# denmark.net
KiCad netlist of a schematic drawn in EAGLE
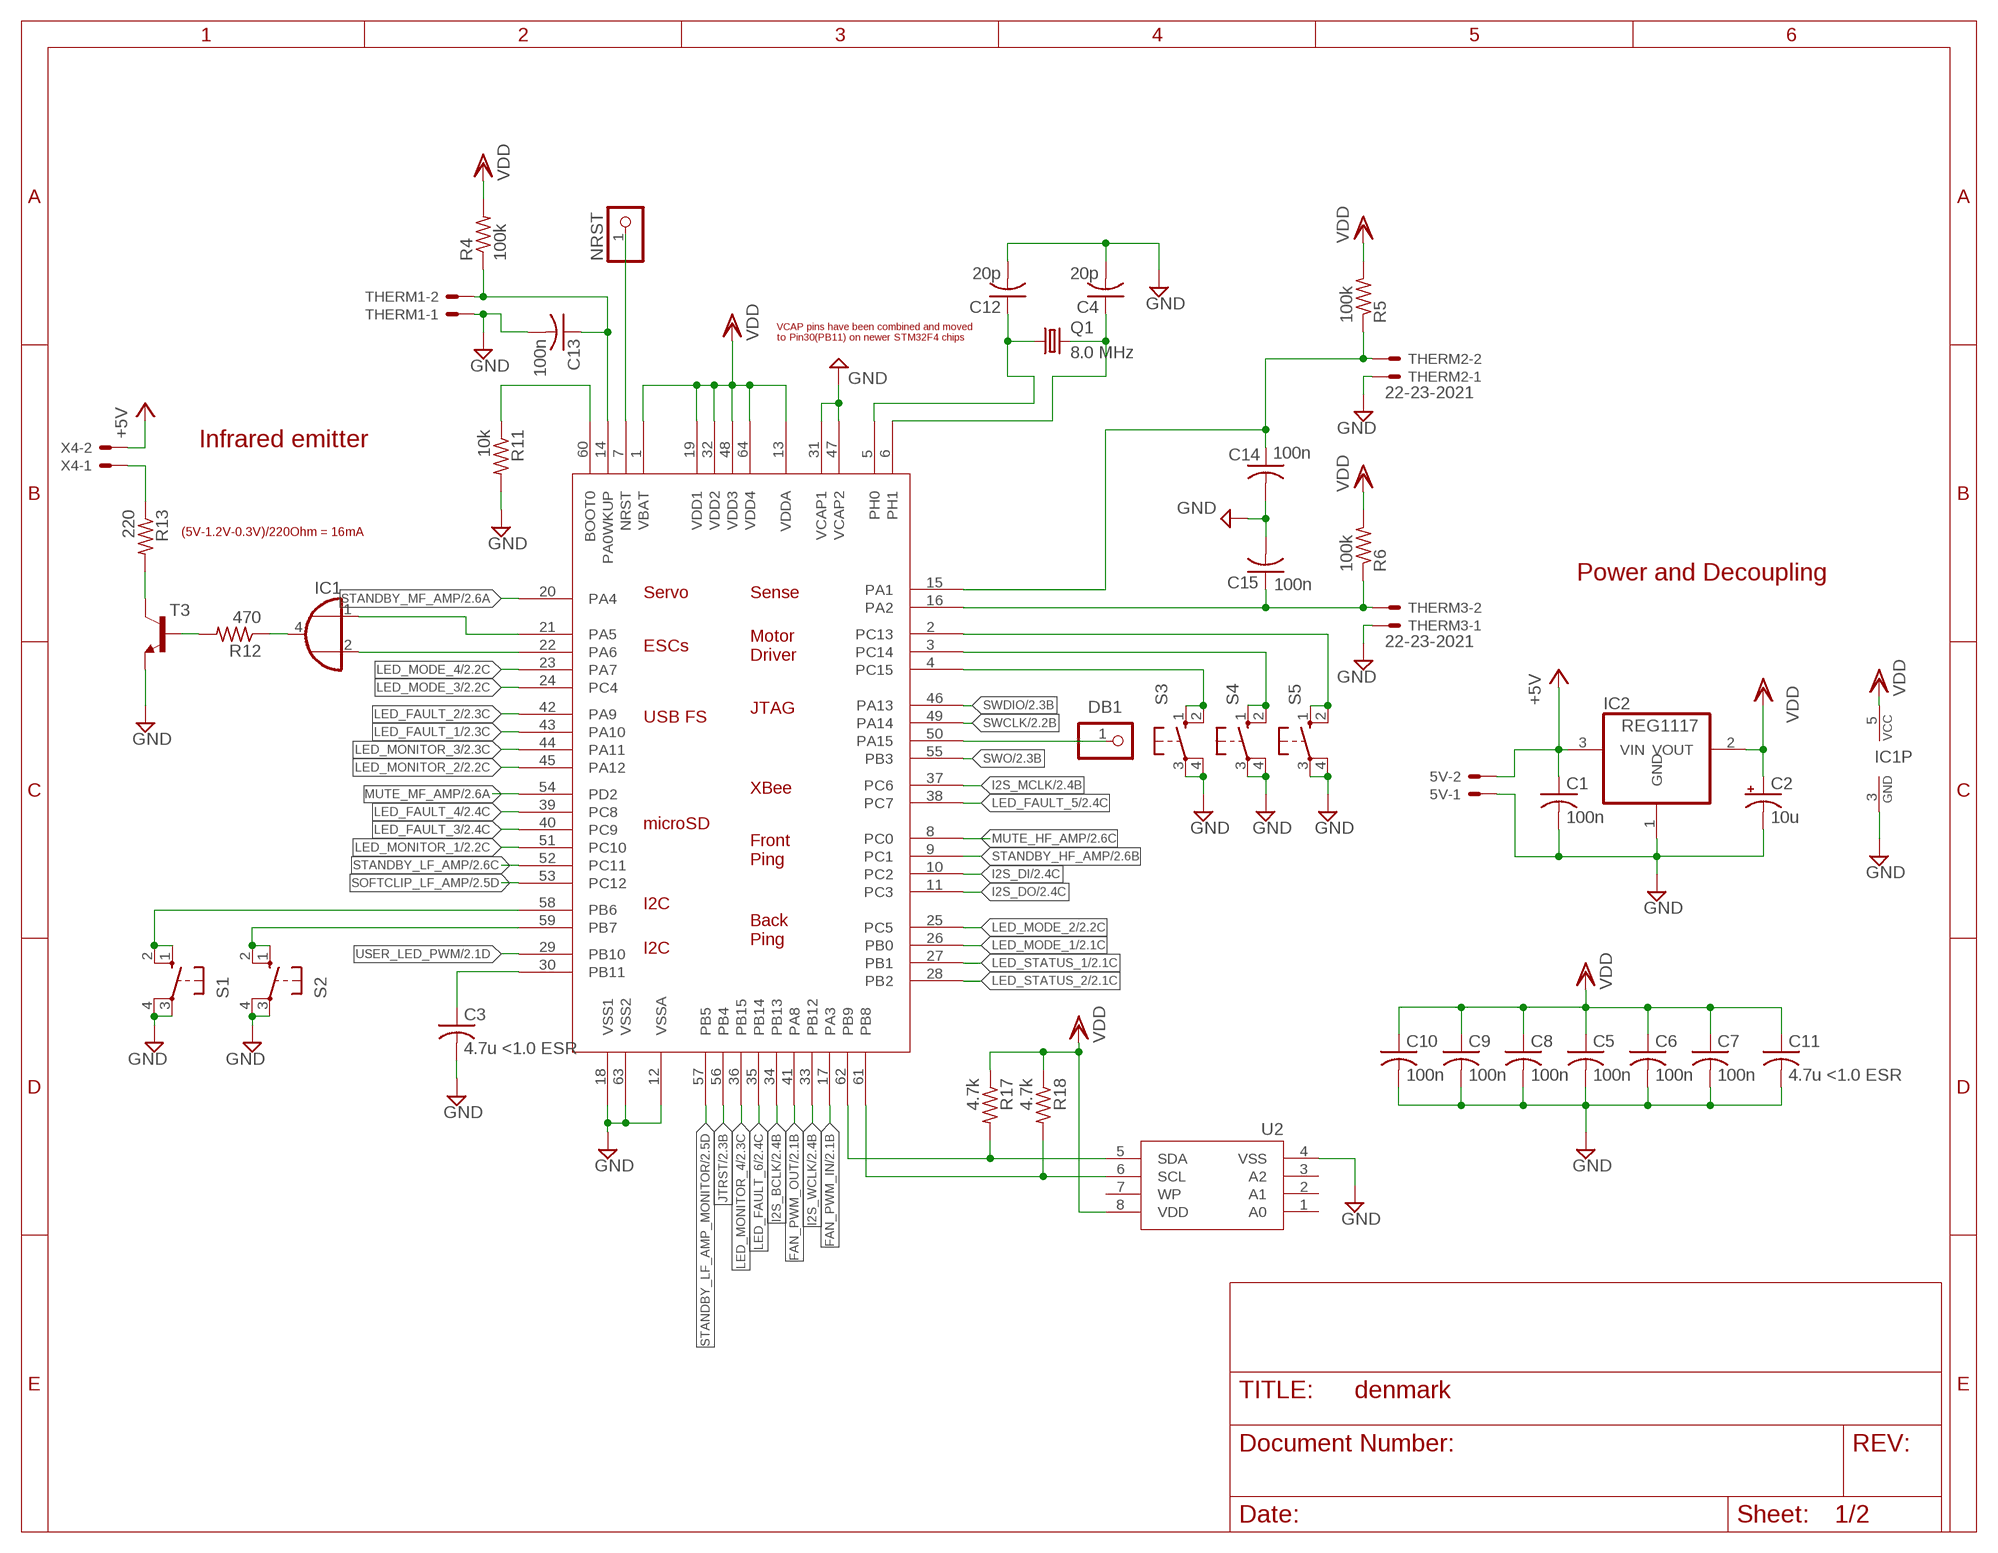
[diagram p0: schematic, sheet 1]
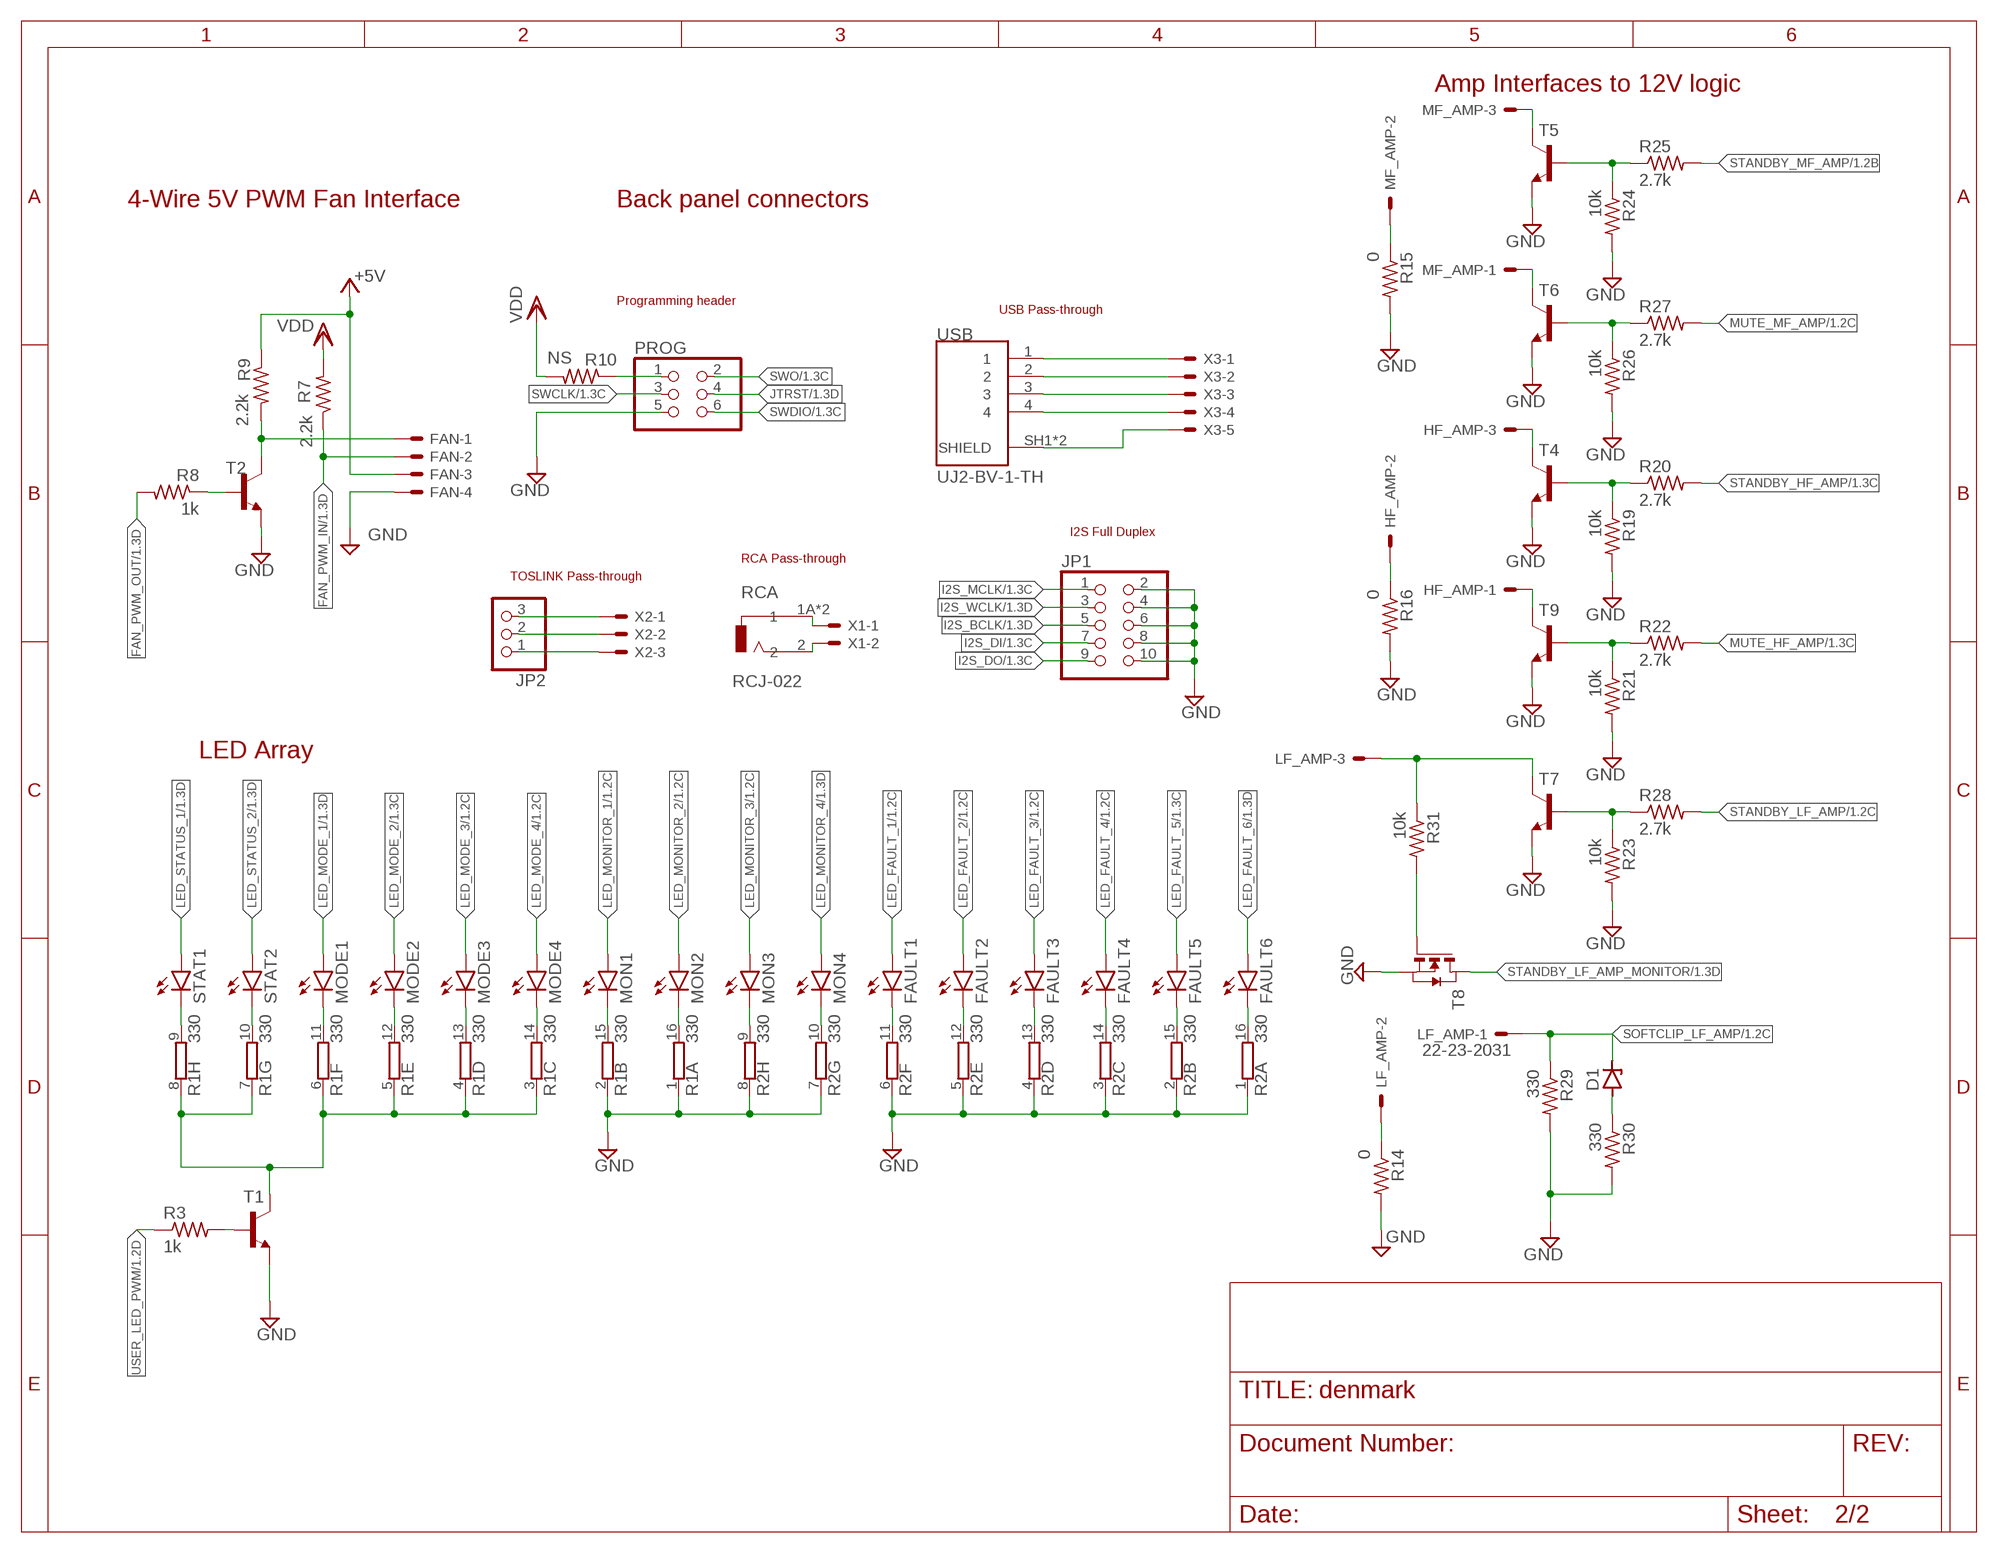
[diagram p1: schematic, sheet 2]

(export (version "E")
  (design (tool "Eeschema 10.0.6"))
  (components
    (comp (ref "D1")
      (value "ZENER-DIODESOD80C")
      (footprint "eagle-import:SOD80C")
      (libsource (lib "eagle-import") (part "ZENER-DIODESOD80C"))
    )
    (comp (ref "FAN")
      (value "22-23-2041")
      (footprint "eagle-import:22-23-2041")
      (fields (field (name "MF") "MOLEX"))
      (libsource (lib "eagle-import") (part "22-23-2041"))
    )
    (comp (ref "FAULT1")
      (value "LEDCHIPLED_0805")
      (footprint "eagle-import:CHIPLED_0805")
      (libsource (lib "eagle-import") (part "LEDCHIPLED_0805"))
    )
    (comp (ref "FAULT2")
      (value "LEDCHIPLED_0805")
      (footprint "eagle-import:CHIPLED_0805")
      (libsource (lib "eagle-import") (part "LEDCHIPLED_0805"))
    )
    (comp (ref "FAULT3")
      (value "LEDCHIPLED_0805")
      (footprint "eagle-import:CHIPLED_0805")
      (libsource (lib "eagle-import") (part "LEDCHIPLED_0805"))
    )
    (comp (ref "FAULT4")
      (value "LEDCHIPLED_0805")
      (footprint "eagle-import:CHIPLED_0805")
      (libsource (lib "eagle-import") (part "LEDCHIPLED_0805"))
    )
    (comp (ref "FAULT5")
      (value "LEDCHIPLED_0805")
      (footprint "eagle-import:CHIPLED_0805")
      (libsource (lib "eagle-import") (part "LEDCHIPLED_0805"))
    )
    (comp (ref "FAULT6")
      (value "LEDCHIPLED_0805")
      (footprint "eagle-import:CHIPLED_0805")
      (libsource (lib "eagle-import") (part "LEDCHIPLED_0805"))
    )
    (comp (ref "HF_AMP")
      (value "22-23-2031")
      (footprint "eagle-import:22-23-2031")
      (fields (field (name "MF") "MOLEX"))
      (libsource (lib "eagle-import") (part "22-23-2031"))
    )
    (comp (ref "JP1")
      (value "PINHD-2X5")
      (footprint "eagle-import:2X05")
      (libsource (lib "eagle-import") (part "PINHD-2X5"))
    )
    (comp (ref "JP2")
      (value "PINHD-1X3")
      (footprint "eagle-import:1X03")
      (libsource (lib "eagle-import") (part "PINHD-1X3"))
    )
    (comp (ref "LF_AMP")
      (value "22-23-2031")
      (footprint "eagle-import:22-23-2031")
      (fields (field (name "MF") "MOLEX"))
      (libsource (lib "eagle-import") (part "22-23-2031"))
    )
    (comp (ref "MF_AMP")
      (value "22-23-2031")
      (footprint "eagle-import:22-23-2031")
      (fields (field (name "MF") "MOLEX"))
      (libsource (lib "eagle-import") (part "22-23-2031"))
    )
    (comp (ref "MODE1")
      (value "LEDCHIPLED_0805")
      (footprint "eagle-import:CHIPLED_0805")
      (libsource (lib "eagle-import") (part "LEDCHIPLED_0805"))
    )
    (comp (ref "MODE2")
      (value "LEDCHIPLED_0805")
      (footprint "eagle-import:CHIPLED_0805")
      (libsource (lib "eagle-import") (part "LEDCHIPLED_0805"))
    )
    (comp (ref "MODE3")
      (value "LEDCHIPLED_0805")
      (footprint "eagle-import:CHIPLED_0805")
      (libsource (lib "eagle-import") (part "LEDCHIPLED_0805"))
    )
    (comp (ref "MODE4")
      (value "LEDCHIPLED_0805")
      (footprint "eagle-import:CHIPLED_0805")
      (libsource (lib "eagle-import") (part "LEDCHIPLED_0805"))
    )
    (comp (ref "MON1")
      (value "LEDCHIPLED_0805")
      (footprint "eagle-import:CHIPLED_0805")
      (libsource (lib "eagle-import") (part "LEDCHIPLED_0805"))
    )
    (comp (ref "MON2")
      (value "LEDCHIPLED_0805")
      (footprint "eagle-import:CHIPLED_0805")
      (libsource (lib "eagle-import") (part "LEDCHIPLED_0805"))
    )
    (comp (ref "MON3")
      (value "LEDCHIPLED_0805")
      (footprint "eagle-import:CHIPLED_0805")
      (libsource (lib "eagle-import") (part "LEDCHIPLED_0805"))
    )
    (comp (ref "MON4")
      (value "LEDCHIPLED_0805")
      (footprint "eagle-import:CHIPLED_0805")
      (libsource (lib "eagle-import") (part "LEDCHIPLED_0805"))
    )
    (comp (ref "PROG")
      (value "PINHD-2X3")
      (footprint "eagle-import:2X03")
      (libsource (lib "eagle-import") (part "PINHD-2X3"))
    )
    (comp (ref "R1")
      (value "330")
      (footprint "eagle-import:SO16")
      (libsource (lib "eagle-import") (part "2NBS16-8E"))
    )
    (comp (ref "R2")
      (value "330")
      (footprint "eagle-import:SO16")
      (libsource (lib "eagle-import") (part "2NBS16-8E"))
    )
    (comp (ref "R3")
      (value "1k")
      (footprint "eagle-import:R0603")
      (libsource (lib "eagle-import") (part "R-US_R0603"))
    )
    (comp (ref "R7")
      (value "2.2k")
      (footprint "eagle-import:R0603")
      (libsource (lib "eagle-import") (part "R-US_R0603"))
    )
    (comp (ref "R8")
      (value "1k")
      (footprint "eagle-import:R0603")
      (libsource (lib "eagle-import") (part "R-US_R0603"))
    )
    (comp (ref "R9")
      (value "2.2k")
      (footprint "eagle-import:R0603")
      (libsource (lib "eagle-import") (part "R-US_R0603"))
    )
    (comp (ref "R10")
      (value "NS")
      (footprint "eagle-import:R0603")
      (libsource (lib "eagle-import") (part "R-US_R0603"))
    )
    (comp (ref "R14")
      (value "0")
      (footprint "eagle-import:R0603")
      (libsource (lib "eagle-import") (part "R-US_R0603"))
    )
    (comp (ref "R15")
      (value "0")
      (footprint "eagle-import:R0603")
      (libsource (lib "eagle-import") (part "R-US_R0603"))
    )
    (comp (ref "R16")
      (value "0")
      (footprint "eagle-import:R0603")
      (libsource (lib "eagle-import") (part "R-US_R0603"))
    )
    (comp (ref "R19")
      (value "10k")
      (footprint "eagle-import:R0603")
      (libsource (lib "eagle-import") (part "R-US_R0603"))
    )
    (comp (ref "R20")
      (value "2.7k")
      (footprint "eagle-import:R0603")
      (libsource (lib "eagle-import") (part "R-US_R0603"))
    )
    (comp (ref "R21")
      (value "10k")
      (footprint "eagle-import:R0603")
      (libsource (lib "eagle-import") (part "R-US_R0603"))
    )
    (comp (ref "R22")
      (value "2.7k")
      (footprint "eagle-import:R0603")
      (libsource (lib "eagle-import") (part "R-US_R0603"))
    )
    (comp (ref "R23")
      (value "10k")
      (footprint "eagle-import:R0603")
      (libsource (lib "eagle-import") (part "R-US_R0603"))
    )
    (comp (ref "R24")
      (value "10k")
      (footprint "eagle-import:R0603")
      (libsource (lib "eagle-import") (part "R-US_R0603"))
    )
    (comp (ref "R25")
      (value "2.7k")
      (footprint "eagle-import:R0603")
      (libsource (lib "eagle-import") (part "R-US_R0603"))
    )
    (comp (ref "R26")
      (value "10k")
      (footprint "eagle-import:R0603")
      (libsource (lib "eagle-import") (part "R-US_R0603"))
    )
    (comp (ref "R27")
      (value "2.7k")
      (footprint "eagle-import:R0603")
      (libsource (lib "eagle-import") (part "R-US_R0603"))
    )
    (comp (ref "R28")
      (value "2.7k")
      (footprint "eagle-import:R0603")
      (libsource (lib "eagle-import") (part "R-US_R0603"))
    )
    (comp (ref "R29")
      (value "330")
      (footprint "eagle-import:R0603")
      (libsource (lib "eagle-import") (part "R-US_R0603"))
    )
    (comp (ref "R30")
      (value "330")
      (footprint "eagle-import:R0603")
      (libsource (lib "eagle-import") (part "R-US_R0603"))
    )
    (comp (ref "R31")
      (value "10k")
      (footprint "eagle-import:R0603")
      (libsource (lib "eagle-import") (part "R-US_R0603"))
    )
    (comp (ref "RCA")
      (value "RCJ-022")
      (footprint "eagle-import:CUI_RCJ-022")
      (fields (field (name "MANUFACTURER") "CUI Inc"))
      (libsource (lib "eagle-import") (part "RCJ-022"))
    )
    (comp (ref "STAT1")
      (value "LEDCHIPLED_0805")
      (footprint "eagle-import:CHIPLED_0805")
      (libsource (lib "eagle-import") (part "LEDCHIPLED_0805"))
    )
    (comp (ref "STAT2")
      (value "LEDCHIPLED_0805")
      (footprint "eagle-import:CHIPLED_0805")
      (libsource (lib "eagle-import") (part "LEDCHIPLED_0805"))
    )
    (comp (ref "T1")
      (value "MMBT3904LT1-NPN-SOT23-BEC")
      (footprint "eagle-import:SOT23-BEC")
      (libsource (lib "eagle-import") (part "-NPN-SOT23-BECMMBT3904LT1"))
    )
    (comp (ref "T2")
      (value "MMBT3904LT1-NPN-SOT23-BEC")
      (footprint "eagle-import:SOT23-BEC")
      (libsource (lib "eagle-import") (part "-NPN-SOT23-BECMMBT3904LT1"))
    )
    (comp (ref "T4")
      (value "MMBT3904LT1-NPN-SOT23-BEC")
      (footprint "eagle-import:SOT23-BEC")
      (libsource (lib "eagle-import") (part "-NPN-SOT23-BECMMBT3904LT1"))
    )
    (comp (ref "T5")
      (value "MMBT3904LT1-NPN-SOT23-BEC")
      (footprint "eagle-import:SOT23-BEC")
      (libsource (lib "eagle-import") (part "-NPN-SOT23-BECMMBT3904LT1"))
    )
    (comp (ref "T6")
      (value "MMBT3904LT1-NPN-SOT23-BEC")
      (footprint "eagle-import:SOT23-BEC")
      (libsource (lib "eagle-import") (part "-NPN-SOT23-BECMMBT3904LT1"))
    )
    (comp (ref "T7")
      (value "MMBT3904LT1-NPN-SOT23-BEC")
      (footprint "eagle-import:SOT23-BEC")
      (libsource (lib "eagle-import") (part "-NPN-SOT23-BECMMBT3904LT1"))
    )
    (comp (ref "T8")
      (value "NMOSSOT23")
      (footprint "eagle-import:SOT-23")
      (libsource (lib "eagle-import") (part "NMOSSOT23"))
    )
    (comp (ref "T9")
      (value "MMBT3904LT1-NPN-SOT23-BEC")
      (footprint "eagle-import:SOT23-BEC")
      (libsource (lib "eagle-import") (part "-NPN-SOT23-BECMMBT3904LT1"))
    )
    (comp (ref "USB")
      (value "UJ2-BV-1-TH")
      (footprint "eagle-import:CUI_UJ2-BV-1-TH")
      (fields (field (name "MANUFACTURER") "CUI INC"))
      (libsource (lib "eagle-import") (part "UJ2-BV-1-TH"))
    )
    (comp (ref "X1")
      (value "22-23-2021")
      (footprint "eagle-import:22-23-2021")
      (fields (field (name "MF") "MOLEX"))
      (libsource (lib "eagle-import") (part "22-23-2021"))
    )
    (comp (ref "X2")
      (value "22-23-2031")
      (footprint "eagle-import:22-23-2031")
      (fields (field (name "MF") "MOLEX"))
      (libsource (lib "eagle-import") (part "22-23-2031"))
    )
    (comp (ref "X3")
      (value "22-23-2051")
      (footprint "eagle-import:22-23-2051")
      (fields (field (name "MF") "MOLEX"))
      (libsource (lib "eagle-import") (part "22-23-2051"))
    )
    (comp (ref "5V")
      (value "22-23-2021")
      (footprint "eagle-import:22-23-2021")
      (fields (field (name "MF") "MOLEX"))
      (libsource (lib "eagle-import") (part "22-23-2021"))
    )
    (comp (ref "C1")
      (value "100n")
      (footprint "eagle-import:C0805")
      (libsource (lib "eagle-import") (part "C-USC0805"))
    )
    (comp (ref "C2")
      (value "10u")
      (footprint "eagle-import:E3,5-8")
      (libsource (lib "eagle-import") (part "CPOL-USE3.5-8"))
    )
    (comp (ref "C3")
      (value "4.7u <1.0 ESR")
      (footprint "eagle-import:C1206")
      (libsource (lib "eagle-import") (part "C-USC1206"))
    )
    (comp (ref "C4")
      (value "20p")
      (footprint "eagle-import:C0603K")
      (libsource (lib "eagle-import") (part "C-USC0603K"))
    )
    (comp (ref "C5")
      (value "100n")
      (footprint "eagle-import:C0603K")
      (libsource (lib "eagle-import") (part "C-USC0603K"))
    )
    (comp (ref "C6")
      (value "100n")
      (footprint "eagle-import:C0603K")
      (libsource (lib "eagle-import") (part "C-USC0603K"))
    )
    (comp (ref "C7")
      (value "100n")
      (footprint "eagle-import:C0603K")
      (libsource (lib "eagle-import") (part "C-USC0603K"))
    )
    (comp (ref "C8")
      (value "100n")
      (footprint "eagle-import:C0603K")
      (libsource (lib "eagle-import") (part "C-USC0603K"))
    )
    (comp (ref "C9")
      (value "100n")
      (footprint "eagle-import:C0603K")
      (libsource (lib "eagle-import") (part "C-USC0603K"))
    )
    (comp (ref "C10")
      (value "100n")
      (footprint "eagle-import:C0603K")
      (libsource (lib "eagle-import") (part "C-USC0603K"))
    )
    (comp (ref "C11")
      (value "4.7u <1.0 ESR")
      (footprint "eagle-import:C1206")
      (libsource (lib "eagle-import") (part "C-USC1206"))
    )
    (comp (ref "C12")
      (value "20p")
      (footprint "eagle-import:C0603K")
      (libsource (lib "eagle-import") (part "C-USC0603K"))
    )
    (comp (ref "C13")
      (value "100n")
      (footprint "eagle-import:C0603K")
      (libsource (lib "eagle-import") (part "C-USC0603K"))
    )
    (comp (ref "C14")
      (value "100n")
      (footprint "eagle-import:C0603K")
      (libsource (lib "eagle-import") (part "C-USC0603K"))
    )
    (comp (ref "C15")
      (value "100n")
      (footprint "eagle-import:C0603K")
      (libsource (lib "eagle-import") (part "C-USC0603K"))
    )
    (comp (ref "DB1")
      (value "PINHD-1X1")
      (footprint "eagle-import:1X01")
      (libsource (lib "eagle-import") (part "PINHD-1X1"))
    )
    (comp (ref "IC1")
      (value "74AHC1G32DBV")
      (footprint "eagle-import:SOT23-5")
      (libsource (lib "eagle-import") (part "741G32DBVAHC"))
    )
    (comp (ref "IC2")
      (value "REG1117")
      (footprint "eagle-import:SOT223")
      (libsource (lib "eagle-import") (part "REG1117"))
    )
    (comp (ref "NRST")
      (value "PINHD-1X1")
      (footprint "eagle-import:1X01")
      (libsource (lib "eagle-import") (part "PINHD-1X1"))
    )
    (comp (ref "Q1")
      (value "8.0 MHz")
      (footprint "eagle-import:HC49U-V")
      (libsource (lib "eagle-import") (part "CRYSTALHC49U-V"))
    )
    (comp (ref "R4")
      (value "100k")
      (footprint "eagle-import:R0603")
      (libsource (lib "eagle-import") (part "R-US_R0603"))
    )
    (comp (ref "R5")
      (value "100k")
      (footprint "eagle-import:R0603")
      (libsource (lib "eagle-import") (part "R-US_R0603"))
    )
    (comp (ref "R6")
      (value "100k")
      (footprint "eagle-import:R0603")
      (libsource (lib "eagle-import") (part "R-US_R0603"))
    )
    (comp (ref "R11")
      (value "10k")
      (footprint "eagle-import:R0603")
      (libsource (lib "eagle-import") (part "R-US_R0603"))
    )
    (comp (ref "R12")
      (value "470")
      (footprint "eagle-import:R0603")
      (libsource (lib "eagle-import") (part "R-US_R0603"))
    )
    (comp (ref "R13")
      (value "220")
      (footprint "eagle-import:R0603")
      (libsource (lib "eagle-import") (part "R-US_R0603"))
    )
    (comp (ref "R17")
      (value "4.7k")
      (footprint "eagle-import:R0603")
      (libsource (lib "eagle-import") (part "R-US_R0603"))
    )
    (comp (ref "R18")
      (value "4.7k")
      (footprint "eagle-import:R0603")
      (libsource (lib "eagle-import") (part "R-US_R0603"))
    )
    (comp (ref "S1")
      (value "10-XX")
      (footprint "eagle-import:B3F-10XX")
      (fields (field (name "MPN") "B3F-1000"))
      (libsource (lib "eagle-import") (part "10-XX"))
    )
    (comp (ref "S2")
      (value "10-XX")
      (footprint "eagle-import:B3F-10XX")
      (fields (field (name "MPN") "B3F-1000"))
      (libsource (lib "eagle-import") (part "10-XX"))
    )
    (comp (ref "S3")
      (value "10-XX")
      (footprint "eagle-import:B3F-10XX")
      (fields (field (name "MPN") "B3F-1000"))
      (libsource (lib "eagle-import") (part "10-XX"))
    )
    (comp (ref "S4")
      (value "10-XX")
      (footprint "eagle-import:B3F-10XX")
      (fields (field (name "MPN") "B3F-1000"))
      (libsource (lib "eagle-import") (part "10-XX"))
    )
    (comp (ref "S5")
      (value "10-XX")
      (footprint "eagle-import:B3F-10XX")
      (fields (field (name "MPN") "B3F-1000"))
      (libsource (lib "eagle-import") (part "10-XX"))
    )
    (comp (ref "T3")
      (value "MMBT3904LT1-NPN-SOT23-BEC")
      (footprint "eagle-import:SOT23-BEC")
      (libsource (lib "eagle-import") (part "-NPN-SOT23-BECMMBT3904LT1"))
    )
    (comp (ref "THERM1")
      (value "22-23-2021")
      (footprint "eagle-import:22-23-2021")
      (fields (field (name "MF") "MOLEX"))
      (libsource (lib "eagle-import") (part "22-23-2021"))
    )
    (comp (ref "THERM2")
      (value "22-23-2021")
      (footprint "eagle-import:22-23-2021")
      (fields (field (name "MF") "MOLEX"))
      (libsource (lib "eagle-import") (part "22-23-2021"))
    )
    (comp (ref "THERM3")
      (value "22-23-2021")
      (footprint "eagle-import:22-23-2021")
      (fields (field (name "MF") "MOLEX"))
      (libsource (lib "eagle-import") (part "22-23-2021"))
    )
    (comp (ref "U1")
      (value "STM32F4_10X10_LQFP64")
      (footprint "eagle-import:LQFP-ST-64-2")
      (libsource (lib "eagle-import") (part "STM32F4_10X10_LQFP64"))
    )
    (comp (ref "U2")
      (value "MB85RCSOIC8")
      (footprint "eagle-import:SOIC8")
      (libsource (lib "eagle-import") (part "MB85RCSOIC8"))
    )
    (comp (ref "X4")
      (value "22-23-2021")
      (footprint "eagle-import:22-23-2021")
      (fields (field (name "MF") "MOLEX"))
      (libsource (lib "eagle-import") (part "22-23-2021"))
    )
  )
  (nets
    (net (code "1") (name "+5V") (class "Default")
      (node (ref "5V") (pin "2") (pinfunction "S_2") (pintype "passive"))
      (node (ref "C1") (pin "1") (pinfunction "1_1") (pintype "passive"))
      (node (ref "FAN") (pin "3") (pinfunction "S_3") (pintype "passive"))
      (node (ref "IC2") (pin "3") (pinfunction "VIN_3") (pintype "input"))
      (node (ref "R9") (pin "1") (pinfunction "1_1") (pintype "passive"))
      (node (ref "X4") (pin "2") (pinfunction "S_2") (pintype "passive"))
    )
    (net (code "2") (name "FAN_PWM_IN") (class "Default")
      (node (ref "FAN") (pin "2") (pinfunction "S_2") (pintype "passive"))
      (node (ref "R7") (pin "1") (pinfunction "1_1") (pintype "passive"))
      (node (ref "U1") (pin "17") (pinfunction "PA3_17") (pintype "bidirectional"))
    )
    (net (code "3") (name "FAN_PWM_OUT") (class "Default")
      (node (ref "R8") (pin "2") (pinfunction "2_2") (pintype "passive"))
      (node (ref "U1") (pin "41") (pinfunction "PA8_41") (pintype "bidirectional"))
    )
    (net (code "4") (name "GND") (class "Default")
      (node (ref "5V") (pin "1") (pinfunction "S_1") (pintype "passive"))
      (node (ref "C1") (pin "2") (pinfunction "2_2") (pintype "passive"))
      (node (ref "C10") (pin "2") (pinfunction "2_2") (pintype "passive"))
      (node (ref "C11") (pin "2") (pinfunction "2_2") (pintype "passive"))
      (node (ref "C12") (pin "2") (pinfunction "2_2") (pintype "passive"))
      (node (ref "C13") (pin "2") (pinfunction "2_2") (pintype "passive"))
      (node (ref "C14") (pin "2") (pinfunction "2_2") (pintype "passive"))
      (node (ref "C15") (pin "2") (pinfunction "2_2") (pintype "passive"))
      (node (ref "C2") (pin "-") (pinfunction "-_-") (pintype "passive"))
      (node (ref "C3") (pin "2") (pinfunction "2_2") (pintype "passive"))
      (node (ref "C4") (pin "2") (pinfunction "2_2") (pintype "passive"))
      (node (ref "C5") (pin "2") (pinfunction "2_2") (pintype "passive"))
      (node (ref "C6") (pin "2") (pinfunction "2_2") (pintype "passive"))
      (node (ref "C7") (pin "2") (pinfunction "2_2") (pintype "passive"))
      (node (ref "C8") (pin "2") (pinfunction "2_2") (pintype "passive"))
      (node (ref "C9") (pin "2") (pinfunction "2_2") (pintype "passive"))
      (node (ref "FAN") (pin "4") (pinfunction "S_4") (pintype "passive"))
      (node (ref "IC1") (pin "3") (pinfunction "GND_3") (pintype "power_in"))
      (node (ref "IC2") (pin "1") (pinfunction "GND_1") (pintype "power_in"))
      (node (ref "JP1") (pin "10") (pinfunction "10_10") (pintype "passive"))
      (node (ref "JP1") (pin "2") (pinfunction "2_2") (pintype "passive"))
      (node (ref "JP1") (pin "4") (pinfunction "4_4") (pintype "passive"))
      (node (ref "JP1") (pin "6") (pinfunction "6_6") (pintype "passive"))
      (node (ref "JP1") (pin "8") (pinfunction "8_8") (pintype "passive"))
      (node (ref "PROG") (pin "5") (pinfunction "5_5") (pintype "passive"))
      (node (ref "R1") (pin "1") (pinfunction "1_1") (pintype "passive"))
      (node (ref "R1") (pin "2") (pinfunction "1_2") (pintype "passive"))
      (node (ref "R11") (pin "2") (pinfunction "2_2") (pintype "passive"))
      (node (ref "R14") (pin "2") (pinfunction "2_2") (pintype "passive"))
      (node (ref "R15") (pin "2") (pinfunction "2_2") (pintype "passive"))
      (node (ref "R16") (pin "2") (pinfunction "2_2") (pintype "passive"))
      (node (ref "R19") (pin "2") (pinfunction "2_2") (pintype "passive"))
      (node (ref "R2") (pin "1") (pinfunction "1_1") (pintype "passive"))
      (node (ref "R2") (pin "2") (pinfunction "1_2") (pintype "passive"))
      (node (ref "R2") (pin "3") (pinfunction "1_3") (pintype "passive"))
      (node (ref "R2") (pin "4") (pinfunction "1_4") (pintype "passive"))
      (node (ref "R2") (pin "5") (pinfunction "1_5") (pintype "passive"))
      (node (ref "R2") (pin "6") (pinfunction "1_6") (pintype "passive"))
      (node (ref "R2") (pin "7") (pinfunction "1_7") (pintype "passive"))
      (node (ref "R2") (pin "8") (pinfunction "1_8") (pintype "passive"))
      (node (ref "R21") (pin "2") (pinfunction "2_2") (pintype "passive"))
      (node (ref "R23") (pin "2") (pinfunction "2_2") (pintype "passive"))
      (node (ref "R24") (pin "2") (pinfunction "2_2") (pintype "passive"))
      (node (ref "R26") (pin "2") (pinfunction "2_2") (pintype "passive"))
      (node (ref "R29") (pin "2") (pinfunction "2_2") (pintype "passive"))
      (node (ref "R30") (pin "2") (pinfunction "2_2") (pintype "passive"))
      (node (ref "S1") (pin "3") (pinfunction "P_3") (pintype "passive"))
      (node (ref "S1") (pin "4") (pinfunction "P1_4") (pintype "passive"))
      (node (ref "S2") (pin "3") (pinfunction "P_3") (pintype "passive"))
      (node (ref "S2") (pin "4") (pinfunction "P1_4") (pintype "passive"))
      (node (ref "S3") (pin "3") (pinfunction "P_3") (pintype "passive"))
      (node (ref "S3") (pin "4") (pinfunction "P1_4") (pintype "passive"))
      (node (ref "S4") (pin "3") (pinfunction "P_3") (pintype "passive"))
      (node (ref "S4") (pin "4") (pinfunction "P1_4") (pintype "passive"))
      (node (ref "S5") (pin "3") (pinfunction "P_3") (pintype "passive"))
      (node (ref "S5") (pin "4") (pinfunction "P1_4") (pintype "passive"))
      (node (ref "T1") (pin "E") (pinfunction "E_E") (pintype "passive"))
      (node (ref "T2") (pin "E") (pinfunction "E_E") (pintype "passive"))
      (node (ref "T3") (pin "E") (pinfunction "E_E") (pintype "passive"))
      (node (ref "T4") (pin "E") (pinfunction "E_E") (pintype "passive"))
      (node (ref "T5") (pin "E") (pinfunction "E_E") (pintype "passive"))
      (node (ref "T6") (pin "E") (pinfunction "E_E") (pintype "passive"))
      (node (ref "T7") (pin "E") (pinfunction "E_E") (pintype "passive"))
      (node (ref "T8") (pin "2") (pinfunction "S_2") (pintype "passive"))
      (node (ref "T9") (pin "E") (pinfunction "E_E") (pintype "passive"))
      (node (ref "THERM1") (pin "1") (pinfunction "S_1") (pintype "passive"))
      (node (ref "THERM2") (pin "1") (pinfunction "S_1") (pintype "passive"))
      (node (ref "THERM3") (pin "1") (pinfunction "S_1") (pintype "passive"))
      (node (ref "U1") (pin "12") (pinfunction "VSSA_12") (pintype "power_in"))
      (node (ref "U1") (pin "18") (pinfunction "VSS1_18") (pintype "power_in"))
      (node (ref "U1") (pin "31") (pinfunction "VCAP1_31") (pintype "bidirectional"))
      (node (ref "U1") (pin "47") (pinfunction "VCAP2_47") (pintype "bidirectional"))
      (node (ref "U1") (pin "63") (pinfunction "VSS2_63") (pintype "power_in"))
      (node (ref "U2") (pin "4") (pinfunction "VSS_4") (pintype "bidirectional"))
    )
    (net (code "5") (name "I2S_BCLK") (class "Default")
      (node (ref "JP1") (pin "5") (pinfunction "5_5") (pintype "passive"))
      (node (ref "U1") (pin "34") (pinfunction "PB13_34") (pintype "bidirectional"))
    )
    (net (code "6") (name "I2S_DI") (class "Default")
      (node (ref "JP1") (pin "7") (pinfunction "7_7") (pintype "passive"))
      (node (ref "U1") (pin "10") (pinfunction "PC2_10") (pintype "bidirectional"))
    )
    (net (code "7") (name "I2S_DO") (class "Default")
      (node (ref "JP1") (pin "9") (pinfunction "9_9") (pintype "passive"))
      (node (ref "U1") (pin "11") (pinfunction "PC3_11") (pintype "bidirectional"))
    )
    (net (code "8") (name "I2S_MCLK") (class "Default")
      (node (ref "JP1") (pin "1") (pinfunction "1_1") (pintype "passive"))
      (node (ref "U1") (pin "37") (pinfunction "PC6_37") (pintype "bidirectional"))
    )
    (net (code "9") (name "I2S_WCLK") (class "Default")
      (node (ref "JP1") (pin "3") (pinfunction "3_3") (pintype "passive"))
      (node (ref "U1") (pin "33") (pinfunction "PB12_33") (pintype "bidirectional"))
    )
    (net (code "10") (name "JTRST") (class "Default")
      (node (ref "PROG") (pin "4") (pinfunction "4_4") (pintype "passive"))
      (node (ref "U1") (pin "56") (pinfunction "PB4_56") (pintype "bidirectional"))
    )
    (net (code "11") (name "LED_FAULT_1") (class "Default")
      (node (ref "FAULT1") (pin "A") (pinfunction "A_A") (pintype "passive"))
      (node (ref "U1") (pin "43") (pinfunction "PA10_43") (pintype "bidirectional"))
    )
    (net (code "12") (name "LED_FAULT_2") (class "Default")
      (node (ref "FAULT2") (pin "A") (pinfunction "A_A") (pintype "passive"))
      (node (ref "U1") (pin "42") (pinfunction "PA9_42") (pintype "bidirectional"))
    )
    (net (code "13") (name "LED_FAULT_3") (class "Default")
      (node (ref "FAULT3") (pin "A") (pinfunction "A_A") (pintype "passive"))
      (node (ref "U1") (pin "40") (pinfunction "PC9_40") (pintype "bidirectional"))
    )
    (net (code "14") (name "LED_FAULT_4") (class "Default")
      (node (ref "FAULT4") (pin "A") (pinfunction "A_A") (pintype "passive"))
      (node (ref "U1") (pin "39") (pinfunction "PC8_39") (pintype "bidirectional"))
    )
    (net (code "15") (name "LED_FAULT_5") (class "Default")
      (node (ref "FAULT5") (pin "A") (pinfunction "A_A") (pintype "passive"))
      (node (ref "U1") (pin "38") (pinfunction "PC7_38") (pintype "bidirectional"))
    )
    (net (code "16") (name "LED_FAULT_6") (class "Default")
      (node (ref "FAULT6") (pin "A") (pinfunction "A_A") (pintype "passive"))
      (node (ref "U1") (pin "35") (pinfunction "PB14_35") (pintype "bidirectional"))
    )
    (net (code "17") (name "LED_MODE_1") (class "Default")
      (node (ref "MODE1") (pin "A") (pinfunction "A_A") (pintype "passive"))
      (node (ref "U1") (pin "26") (pinfunction "PB0_26") (pintype "bidirectional"))
    )
    (net (code "18") (name "LED_MODE_2") (class "Default")
      (node (ref "MODE2") (pin "A") (pinfunction "A_A") (pintype "passive"))
      (node (ref "U1") (pin "25") (pinfunction "PC5_25") (pintype "bidirectional"))
    )
    (net (code "19") (name "LED_MODE_3") (class "Default")
      (node (ref "MODE3") (pin "A") (pinfunction "A_A") (pintype "passive"))
      (node (ref "U1") (pin "24") (pinfunction "PC4_24") (pintype "bidirectional"))
    )
    (net (code "20") (name "LED_MODE_4") (class "Default")
      (node (ref "MODE4") (pin "A") (pinfunction "A_A") (pintype "passive"))
      (node (ref "U1") (pin "23") (pinfunction "PA7_23") (pintype "bidirectional"))
    )
    (net (code "21") (name "LED_MONITOR_1") (class "Default")
      (node (ref "MON1") (pin "A") (pinfunction "A_A") (pintype "passive"))
      (node (ref "U1") (pin "51") (pinfunction "PC10_51") (pintype "bidirectional"))
    )
    (net (code "22") (name "LED_MONITOR_2") (class "Default")
      (node (ref "MON2") (pin "A") (pinfunction "A_A") (pintype "passive"))
      (node (ref "U1") (pin "45") (pinfunction "PA12_45") (pintype "bidirectional"))
    )
    (net (code "23") (name "LED_MONITOR_3") (class "Default")
      (node (ref "MON3") (pin "A") (pinfunction "A_A") (pintype "passive"))
      (node (ref "U1") (pin "44") (pinfunction "PA11_44") (pintype "bidirectional"))
    )
    (net (code "24") (name "LED_MONITOR_4") (class "Default")
      (node (ref "MON4") (pin "A") (pinfunction "A_A") (pintype "passive"))
      (node (ref "U1") (pin "36") (pinfunction "PB15_36") (pintype "bidirectional"))
    )
    (net (code "25") (name "LED_STATUS_1") (class "Default")
      (node (ref "STAT1") (pin "A") (pinfunction "A_A") (pintype "passive"))
      (node (ref "U1") (pin "27") (pinfunction "PB1_27") (pintype "bidirectional"))
    )
    (net (code "26") (name "LED_STATUS_2") (class "Default")
      (node (ref "STAT2") (pin "A") (pinfunction "A_A") (pintype "passive"))
      (node (ref "U1") (pin "28") (pinfunction "PB2_28") (pintype "bidirectional"))
    )
    (net (code "27") (name "MUTE_HF_AMP") (class "Default")
      (node (ref "R22") (pin "2") (pinfunction "2_2") (pintype "passive"))
      (node (ref "U1") (pin "8") (pinfunction "PC0_8") (pintype "bidirectional"))
    )
    (net (code "28") (name "MUTE_MF_AMP") (class "Default")
      (node (ref "R27") (pin "2") (pinfunction "2_2") (pintype "passive"))
      (node (ref "U1") (pin "54") (pinfunction "PD2_54") (pintype "bidirectional"))
    )
    (net (code "29") (name "Net-(D1-PadA)") (class "Default")
      (node (ref "D1") (pin "A") (pinfunction "A_A") (pintype "passive"))
      (node (ref "R30") (pin "1") (pinfunction "1_1") (pintype "passive"))
    )
    (net (code "30") (name "Net-(FANA-S)") (class "Default")
      (node (ref "FAN") (pin "1") (pinfunction "S_1") (pintype "passive"))
      (node (ref "R9") (pin "2") (pinfunction "2_2") (pintype "passive"))
      (node (ref "T2") (pin "C") (pinfunction "C_C") (pintype "passive"))
    )
    (net (code "31") (name "Net-(HF_AMPA-S)") (class "Default")
      (node (ref "HF_AMP") (pin "1") (pinfunction "S_1") (pintype "passive"))
      (node (ref "T9") (pin "C") (pinfunction "C_C") (pintype "passive"))
    )
    (net (code "32") (name "Net-(HF_AMPB-S)") (class "Default")
      (node (ref "HF_AMP") (pin "2") (pinfunction "S_2") (pintype "passive"))
      (node (ref "R16") (pin "1") (pinfunction "1_1") (pintype "passive"))
    )
    (net (code "33") (name "Net-(HF_AMPC-S)") (class "Default")
      (node (ref "HF_AMP") (pin "3") (pinfunction "S_3") (pintype "passive"))
      (node (ref "T4") (pin "C") (pinfunction "C_C") (pintype "passive"))
    )
    (net (code "34") (name "Net-(IC1A-I0)") (class "Default")
      (node (ref "IC1") (pin "1") (pinfunction "I0_1") (pintype "input"))
      (node (ref "U1") (pin "21") (pinfunction "PA5_21") (pintype "bidirectional"))
    )
    (net (code "35") (name "Net-(IC1A-I1)") (class "Default")
      (node (ref "IC1") (pin "2") (pinfunction "I1_2") (pintype "input"))
      (node (ref "U1") (pin "22") (pinfunction "PA6_22") (pintype "bidirectional"))
    )
    (net (code "36") (name "Net-(IC1A-O)") (class "Default")
      (node (ref "IC1") (pin "4") (pinfunction "O_4") (pintype "output"))
      (node (ref "R12") (pin "1") (pinfunction "1_1") (pintype "passive"))
    )
    (net (code "37") (name "Net-(LF_AMPB-S)") (class "Default")
      (node (ref "LF_AMP") (pin "2") (pinfunction "S_2") (pintype "passive"))
      (node (ref "R14") (pin "1") (pinfunction "1_1") (pintype "passive"))
    )
    (net (code "38") (name "Net-(LF_AMPC-S)") (class "Default")
      (node (ref "LF_AMP") (pin "3") (pinfunction "S_3") (pintype "passive"))
      (node (ref "R31") (pin "1") (pinfunction "1_1") (pintype "passive"))
      (node (ref "T7") (pin "C") (pinfunction "C_C") (pintype "passive"))
    )
    (net (code "39") (name "Net-(MF_AMPA-S)") (class "Default")
      (node (ref "MF_AMP") (pin "1") (pinfunction "S_1") (pintype "passive"))
      (node (ref "T6") (pin "C") (pinfunction "C_C") (pintype "passive"))
    )
    (net (code "40") (name "Net-(MF_AMPB-S)") (class "Default")
      (node (ref "MF_AMP") (pin "2") (pinfunction "S_2") (pintype "passive"))
      (node (ref "R15") (pin "1") (pinfunction "1_1") (pintype "passive"))
    )
    (net (code "41") (name "Net-(MF_AMPC-S)") (class "Default")
      (node (ref "MF_AMP") (pin "3") (pinfunction "S_3") (pintype "passive"))
      (node (ref "T5") (pin "C") (pinfunction "C_C") (pintype "passive"))
    )
    (net (code "42") (name "Net-(PROG-Pad1)") (class "Default")
      (node (ref "PROG") (pin "1") (pinfunction "1_1") (pintype "passive"))
      (node (ref "R10") (pin "1") (pinfunction "1_1") (pintype "passive"))
    )
    (net (code "43") (name "Net-(R1A-2)") (class "Default")
      (node (ref "MON2") (pin "C") (pinfunction "C_C") (pintype "passive"))
      (node (ref "R1") (pin "16") (pinfunction "2_16") (pintype "passive"))
    )
    (net (code "44") (name "Net-(R1B-2)") (class "Default")
      (node (ref "MON1") (pin "C") (pinfunction "C_C") (pintype "passive"))
      (node (ref "R1") (pin "15") (pinfunction "2_15") (pintype "passive"))
    )
    (net (code "45") (name "Net-(R1C-1)") (class "Default")
      (node (ref "R1") (pin "3") (pinfunction "1_3") (pintype "passive"))
      (node (ref "R1") (pin "4") (pinfunction "1_4") (pintype "passive"))
      (node (ref "R1") (pin "5") (pinfunction "1_5") (pintype "passive"))
      (node (ref "R1") (pin "6") (pinfunction "1_6") (pintype "passive"))
      (node (ref "R1") (pin "7") (pinfunction "1_7") (pintype "passive"))
      (node (ref "R1") (pin "8") (pinfunction "1_8") (pintype "passive"))
      (node (ref "T1") (pin "C") (pinfunction "C_C") (pintype "passive"))
    )
    (net (code "46") (name "Net-(R1C-2)") (class "Default")
      (node (ref "MODE4") (pin "C") (pinfunction "C_C") (pintype "passive"))
      (node (ref "R1") (pin "14") (pinfunction "2_14") (pintype "passive"))
    )
    (net (code "47") (name "Net-(R1D-2)") (class "Default")
      (node (ref "MODE3") (pin "C") (pinfunction "C_C") (pintype "passive"))
      (node (ref "R1") (pin "13") (pinfunction "2_13") (pintype "passive"))
    )
    (net (code "48") (name "Net-(R1E-2)") (class "Default")
      (node (ref "MODE2") (pin "C") (pinfunction "C_C") (pintype "passive"))
      (node (ref "R1") (pin "12") (pinfunction "2_12") (pintype "passive"))
    )
    (net (code "49") (name "Net-(R1F-2)") (class "Default")
      (node (ref "MODE1") (pin "C") (pinfunction "C_C") (pintype "passive"))
      (node (ref "R1") (pin "11") (pinfunction "2_11") (pintype "passive"))
    )
    (net (code "50") (name "Net-(R1G-2)") (class "Default")
      (node (ref "R1") (pin "10") (pinfunction "2_10") (pintype "passive"))
      (node (ref "STAT2") (pin "C") (pinfunction "C_C") (pintype "passive"))
    )
    (net (code "51") (name "Net-(R1H-2)") (class "Default")
      (node (ref "R1") (pin "9") (pinfunction "2_9") (pintype "passive"))
      (node (ref "STAT1") (pin "C") (pinfunction "C_C") (pintype "passive"))
    )
    (net (code "52") (name "Net-(R2A-2)") (class "Default")
      (node (ref "FAULT6") (pin "C") (pinfunction "C_C") (pintype "passive"))
      (node (ref "R2") (pin "16") (pinfunction "2_16") (pintype "passive"))
    )
    (net (code "53") (name "Net-(R2B-2)") (class "Default")
      (node (ref "FAULT5") (pin "C") (pinfunction "C_C") (pintype "passive"))
      (node (ref "R2") (pin "15") (pinfunction "2_15") (pintype "passive"))
    )
    (net (code "54") (name "Net-(R2C-2)") (class "Default")
      (node (ref "FAULT4") (pin "C") (pinfunction "C_C") (pintype "passive"))
      (node (ref "R2") (pin "14") (pinfunction "2_14") (pintype "passive"))
    )
    (net (code "55") (name "Net-(R2D-2)") (class "Default")
      (node (ref "FAULT3") (pin "C") (pinfunction "C_C") (pintype "passive"))
      (node (ref "R2") (pin "13") (pinfunction "2_13") (pintype "passive"))
    )
    (net (code "56") (name "Net-(R2E-2)") (class "Default")
      (node (ref "FAULT2") (pin "C") (pinfunction "C_C") (pintype "passive"))
      (node (ref "R2") (pin "12") (pinfunction "2_12") (pintype "passive"))
    )
    (net (code "57") (name "Net-(R2F-2)") (class "Default")
      (node (ref "FAULT1") (pin "C") (pinfunction "C_C") (pintype "passive"))
      (node (ref "R2") (pin "11") (pinfunction "2_11") (pintype "passive"))
    )
    (net (code "58") (name "Net-(R2G-2)") (class "Default")
      (node (ref "MON4") (pin "C") (pinfunction "C_C") (pintype "passive"))
      (node (ref "R2") (pin "10") (pinfunction "2_10") (pintype "passive"))
    )
    (net (code "59") (name "Net-(R2H-2)") (class "Default")
      (node (ref "MON3") (pin "C") (pinfunction "C_C") (pintype "passive"))
      (node (ref "R2") (pin "9") (pinfunction "2_9") (pintype "passive"))
    )
    (net (code "60") (name "Net-(R3-Pad2)") (class "Default")
      (node (ref "R3") (pin "2") (pinfunction "2_2") (pintype "passive"))
      (node (ref "T1") (pin "B") (pinfunction "B_B") (pintype "passive"))
    )
    (net (code "61") (name "Net-(R8-Pad1)") (class "Default")
      (node (ref "R8") (pin "1") (pinfunction "1_1") (pintype "passive"))
      (node (ref "T2") (pin "B") (pinfunction "B_B") (pintype "passive"))
    )
    (net (code "62") (name "Net-(R12-Pad2)") (class "Default")
      (node (ref "R12") (pin "2") (pinfunction "2_2") (pintype "passive"))
      (node (ref "T3") (pin "B") (pinfunction "B_B") (pintype "passive"))
    )
    (net (code "63") (name "Net-(R13-Pad2)") (class "Default")
      (node (ref "R13") (pin "2") (pinfunction "2_2") (pintype "passive"))
      (node (ref "T3") (pin "C") (pinfunction "C_C") (pintype "passive"))
    )
    (net (code "64") (name "Net-(R19-Pad1)") (class "Default")
      (node (ref "R19") (pin "1") (pinfunction "1_1") (pintype "passive"))
      (node (ref "R20") (pin "1") (pinfunction "1_1") (pintype "passive"))
      (node (ref "T4") (pin "B") (pinfunction "B_B") (pintype "passive"))
    )
    (net (code "65") (name "Net-(R21-Pad1)") (class "Default")
      (node (ref "R21") (pin "1") (pinfunction "1_1") (pintype "passive"))
      (node (ref "R22") (pin "1") (pinfunction "1_1") (pintype "passive"))
      (node (ref "T9") (pin "B") (pinfunction "B_B") (pintype "passive"))
    )
    (net (code "66") (name "Net-(R23-Pad1)") (class "Default")
      (node (ref "R23") (pin "1") (pinfunction "1_1") (pintype "passive"))
      (node (ref "R28") (pin "1") (pinfunction "1_1") (pintype "passive"))
      (node (ref "T7") (pin "B") (pinfunction "B_B") (pintype "passive"))
    )
    (net (code "67") (name "Net-(R24-Pad1)") (class "Default")
      (node (ref "R24") (pin "1") (pinfunction "1_1") (pintype "passive"))
      (node (ref "R25") (pin "1") (pinfunction "1_1") (pintype "passive"))
      (node (ref "T5") (pin "B") (pinfunction "B_B") (pintype "passive"))
    )
    (net (code "68") (name "Net-(R26-Pad1)") (class "Default")
      (node (ref "R26") (pin "1") (pinfunction "1_1") (pintype "passive"))
      (node (ref "R27") (pin "1") (pinfunction "1_1") (pintype "passive"))
      (node (ref "T6") (pin "B") (pinfunction "B_B") (pintype "passive"))
    )
    (net (code "69") (name "Net-(S1-S)") (class "Default")
      (node (ref "S1") (pin "1") (pinfunction "S_1") (pintype "passive"))
      (node (ref "S1") (pin "2") (pinfunction "S1_2") (pintype "passive"))
      (node (ref "U1") (pin "58") (pinfunction "PB6_58") (pintype "bidirectional"))
    )
    (net (code "70") (name "Net-(S2-S)") (class "Default")
      (node (ref "S2") (pin "1") (pinfunction "S_1") (pintype "passive"))
      (node (ref "S2") (pin "2") (pinfunction "S1_2") (pintype "passive"))
      (node (ref "U1") (pin "59") (pinfunction "PB7_59") (pintype "bidirectional"))
    )
    (net (code "71") (name "Net-(S3-S)") (class "Default")
      (node (ref "S3") (pin "1") (pinfunction "S_1") (pintype "passive"))
      (node (ref "S3") (pin "2") (pinfunction "S1_2") (pintype "passive"))
      (node (ref "U1") (pin "4") (pinfunction "PC15_4") (pintype "bidirectional"))
    )
    (net (code "72") (name "Net-(S4-S)") (class "Default")
      (node (ref "S4") (pin "1") (pinfunction "S_1") (pintype "passive"))
      (node (ref "S4") (pin "2") (pinfunction "S1_2") (pintype "passive"))
      (node (ref "U1") (pin "3") (pinfunction "PC14_3") (pintype "bidirectional"))
    )
    (net (code "73") (name "Net-(S5-S)") (class "Default")
      (node (ref "S5") (pin "1") (pinfunction "S_1") (pintype "passive"))
      (node (ref "S5") (pin "2") (pinfunction "S1_2") (pintype "passive"))
      (node (ref "U1") (pin "2") (pinfunction "PC13_2") (pintype "bidirectional"))
    )
    (net (code "74") (name "Net-(T8-G)") (class "Default")
      (node (ref "R31") (pin "2") (pinfunction "2_2") (pintype "passive"))
      (node (ref "T8") (pin "3") (pinfunction "G_3") (pintype "passive"))
    )
    (net (code "75") (name "Net-(THERM1B-S)") (class "Default")
      (node (ref "C13") (pin "1") (pinfunction "1_1") (pintype "passive"))
      (node (ref "R4") (pin "1") (pinfunction "1_1") (pintype "passive"))
      (node (ref "THERM1") (pin "2") (pinfunction "S_2") (pintype "passive"))
      (node (ref "U1") (pin "14") (pinfunction "PA0WKUP_14") (pintype "bidirectional"))
    )
    (net (code "76") (name "Net-(THERM2B-S)") (class "Default")
      (node (ref "C14") (pin "1") (pinfunction "1_1") (pintype "passive"))
      (node (ref "R5") (pin "1") (pinfunction "1_1") (pintype "passive"))
      (node (ref "THERM2") (pin "2") (pinfunction "S_2") (pintype "passive"))
      (node (ref "U1") (pin "15") (pinfunction "PA1_15") (pintype "bidirectional"))
    )
    (net (code "77") (name "Net-(THERM3B-S)") (class "Default")
      (node (ref "C15") (pin "1") (pinfunction "1_1") (pintype "passive"))
      (node (ref "R6") (pin "1") (pinfunction "1_1") (pintype "passive"))
      (node (ref "THERM3") (pin "2") (pinfunction "S_2") (pintype "passive"))
      (node (ref "U1") (pin "16") (pinfunction "PA2_16") (pintype "bidirectional"))
    )
    (net (code "78") (name "Net-(U1-BOOT0)") (class "Default")
      (node (ref "R11") (pin "1") (pinfunction "1_1") (pintype "passive"))
      (node (ref "U1") (pin "60") (pinfunction "BOOT0_60") (pintype "bidirectional"))
    )
    (net (code "79") (name "Net-(U1-NRST)") (class "Default")
      (node (ref "NRST") (pin "1") (pinfunction "1_1") (pintype "passive"))
      (node (ref "U1") (pin "7") (pinfunction "NRST_7") (pintype "bidirectional"))
    )
    (net (code "80") (name "Net-(U1-PA15)") (class "Default")
      (node (ref "DB1") (pin "1") (pinfunction "1_1") (pintype "passive"))
      (node (ref "U1") (pin "50") (pinfunction "PA15_50") (pintype "bidirectional"))
    )
    (net (code "81") (name "Net-(U1-PB8)") (class "Default")
      (node (ref "R18") (pin "2") (pinfunction "2_2") (pintype "passive"))
      (node (ref "U1") (pin "61") (pinfunction "PB8_61") (pintype "bidirectional"))
      (node (ref "U2") (pin "6") (pinfunction "SCL_6") (pintype "bidirectional"))
    )
    (net (code "82") (name "Net-(U1-PB9)") (class "Default")
      (node (ref "R17") (pin "2") (pinfunction "2_2") (pintype "passive"))
      (node (ref "U1") (pin "62") (pinfunction "PB9_62") (pintype "bidirectional"))
      (node (ref "U2") (pin "5") (pinfunction "SDA_5") (pintype "bidirectional"))
    )
    (net (code "83") (name "Net-(U1-PB11)") (class "Default")
      (node (ref "C3") (pin "1") (pinfunction "1_1") (pintype "passive"))
      (node (ref "U1") (pin "30") (pinfunction "PB11_30") (pintype "bidirectional"))
    )
    (net (code "84") (name "Net-(U1-PH0)") (class "Default")
      (node (ref "C12") (pin "1") (pinfunction "1_1") (pintype "passive"))
      (node (ref "Q1") (pin "1") (pinfunction "1_1") (pintype "passive"))
      (node (ref "U1") (pin "5") (pinfunction "PH0_5") (pintype "bidirectional"))
    )
    (net (code "85") (name "Net-(U1-PH1)") (class "Default")
      (node (ref "C4") (pin "1") (pinfunction "1_1") (pintype "passive"))
      (node (ref "Q1") (pin "2") (pinfunction "2_2") (pintype "passive"))
      (node (ref "U1") (pin "6") (pinfunction "PH1_6") (pintype "bidirectional"))
    )
    (net (code "86") (name "Net-(X1A-S)") (class "Default")
      (node (ref "RCA") (pin "1A") (pinfunction "1_1A") (pintype "passive"))
      (node (ref "RCA") (pin "1B") (pinfunction "1_1B") (pintype "passive"))
      (node (ref "X1") (pin "1") (pinfunction "S_1") (pintype "passive"))
    )
    (net (code "87") (name "Net-(X1B-S)") (class "Default")
      (node (ref "RCA") (pin "2") (pinfunction "2_2") (pintype "passive"))
      (node (ref "X1") (pin "2") (pinfunction "S_2") (pintype "passive"))
    )
    (net (code "88") (name "Net-(X2A-S)") (class "Default")
      (node (ref "JP2") (pin "3") (pinfunction "3_3") (pintype "passive"))
      (node (ref "X2") (pin "1") (pinfunction "S_1") (pintype "passive"))
    )
    (net (code "89") (name "Net-(X2B-S)") (class "Default")
      (node (ref "JP2") (pin "2") (pinfunction "2_2") (pintype "passive"))
      (node (ref "X2") (pin "2") (pinfunction "S_2") (pintype "passive"))
    )
    (net (code "90") (name "Net-(X2C-S)") (class "Default")
      (node (ref "JP2") (pin "1") (pinfunction "1_1") (pintype "passive"))
      (node (ref "X2") (pin "3") (pinfunction "S_3") (pintype "passive"))
    )
    (net (code "91") (name "Net-(X3A-S)") (class "Default")
      (node (ref "USB") (pin "1") (pinfunction "1_1") (pintype "passive"))
      (node (ref "X3") (pin "1") (pinfunction "S_1") (pintype "passive"))
    )
    (net (code "92") (name "Net-(X3B-S)") (class "Default")
      (node (ref "USB") (pin "2") (pinfunction "2_2") (pintype "passive"))
      (node (ref "X3") (pin "2") (pinfunction "S_2") (pintype "passive"))
    )
    (net (code "93") (name "Net-(X3C-S)") (class "Default")
      (node (ref "USB") (pin "3") (pinfunction "3_3") (pintype "passive"))
      (node (ref "X3") (pin "3") (pinfunction "S_3") (pintype "passive"))
    )
    (net (code "94") (name "Net-(X3D-S)") (class "Default")
      (node (ref "USB") (pin "4") (pinfunction "4_4") (pintype "passive"))
      (node (ref "X3") (pin "4") (pinfunction "S_4") (pintype "passive"))
    )
    (net (code "95") (name "Net-(X3E-S)") (class "Default")
      (node (ref "USB") (pin "SH1") (pinfunction "SHIELD_SH1") (pintype "passive"))
      (node (ref "USB") (pin "SH2") (pinfunction "SHIELD_SH2") (pintype "passive"))
      (node (ref "X3") (pin "5") (pinfunction "S_5") (pintype "passive"))
    )
    (net (code "96") (name "Net-(X4A-S)") (class "Default")
      (node (ref "R13") (pin "1") (pinfunction "1_1") (pintype "passive"))
      (node (ref "X4") (pin "1") (pinfunction "S_1") (pintype "passive"))
    )
    (net (code "97") (name "SOFTCLIP_LF_AMP") (class "Default")
      (node (ref "D1") (pin "C") (pinfunction "C_C") (pintype "passive"))
      (node (ref "LF_AMP") (pin "1") (pinfunction "S_1") (pintype "passive"))
      (node (ref "R29") (pin "1") (pinfunction "1_1") (pintype "passive"))
      (node (ref "U1") (pin "53") (pinfunction "PC12_53") (pintype "bidirectional"))
    )
    (net (code "98") (name "STANDBY_HF_AMP") (class "Default")
      (node (ref "R20") (pin "2") (pinfunction "2_2") (pintype "passive"))
      (node (ref "U1") (pin "9") (pinfunction "PC1_9") (pintype "bidirectional"))
    )
    (net (code "99") (name "STANDBY_LF_AMP") (class "Default")
      (node (ref "R28") (pin "2") (pinfunction "2_2") (pintype "passive"))
      (node (ref "U1") (pin "52") (pinfunction "PC11_52") (pintype "bidirectional"))
    )
    (net (code "100") (name "STANDBY_LF_AMP_MONITOR") (class "Default")
      (node (ref "T8") (pin "1") (pinfunction "D_1") (pintype "passive"))
      (node (ref "U1") (pin "57") (pinfunction "PB5_57") (pintype "bidirectional"))
    )
    (net (code "101") (name "STANDBY_MF_AMP") (class "Default")
      (node (ref "R25") (pin "2") (pinfunction "2_2") (pintype "passive"))
      (node (ref "U1") (pin "20") (pinfunction "PA4_20") (pintype "bidirectional"))
    )
    (net (code "102") (name "SWCLK") (class "Default")
      (node (ref "PROG") (pin "3") (pinfunction "3_3") (pintype "passive"))
      (node (ref "U1") (pin "49") (pinfunction "PA14_49") (pintype "bidirectional"))
    )
    (net (code "103") (name "SWDIO") (class "Default")
      (node (ref "PROG") (pin "6") (pinfunction "6_6") (pintype "passive"))
      (node (ref "U1") (pin "46") (pinfunction "PA13_46") (pintype "bidirectional"))
    )
    (net (code "104") (name "SWO") (class "Default")
      (node (ref "PROG") (pin "2") (pinfunction "2_2") (pintype "passive"))
      (node (ref "U1") (pin "55") (pinfunction "PB3_55") (pintype "bidirectional"))
    )
    (net (code "105") (name "USER_LED_PWM") (class "Default")
      (node (ref "R3") (pin "1") (pinfunction "1_1") (pintype "passive"))
      (node (ref "U1") (pin "29") (pinfunction "PB10_29") (pintype "bidirectional"))
    )
    (net (code "106") (name "VDD") (class "Default")
      (node (ref "C10") (pin "1") (pinfunction "1_1") (pintype "passive"))
      (node (ref "C11") (pin "1") (pinfunction "1_1") (pintype "passive"))
      (node (ref "C2") (pin "+") (pinfunction "+_+") (pintype "passive"))
      (node (ref "C5") (pin "1") (pinfunction "1_1") (pintype "passive"))
      (node (ref "C6") (pin "1") (pinfunction "1_1") (pintype "passive"))
      (node (ref "C7") (pin "1") (pinfunction "1_1") (pintype "passive"))
      (node (ref "C8") (pin "1") (pinfunction "1_1") (pintype "passive"))
      (node (ref "C9") (pin "1") (pinfunction "1_1") (pintype "passive"))
      (node (ref "IC1") (pin "5") (pinfunction "VCC_5") (pintype "power_in"))
      (node (ref "IC2") (pin "2") (pinfunction "VOUT_2") (pintype "output"))
      (node (ref "R10") (pin "2") (pinfunction "2_2") (pintype "passive"))
      (node (ref "R17") (pin "1") (pinfunction "1_1") (pintype "passive"))
      (node (ref "R18") (pin "1") (pinfunction "1_1") (pintype "passive"))
      (node (ref "R4") (pin "2") (pinfunction "2_2") (pintype "passive"))
      (node (ref "R5") (pin "2") (pinfunction "2_2") (pintype "passive"))
      (node (ref "R6") (pin "2") (pinfunction "2_2") (pintype "passive"))
      (node (ref "R7") (pin "2") (pinfunction "2_2") (pintype "passive"))
      (node (ref "U1") (pin "1") (pinfunction "VBAT_1") (pintype "bidirectional"))
      (node (ref "U1") (pin "13") (pinfunction "VDDA_13") (pintype "power_in"))
      (node (ref "U1") (pin "19") (pinfunction "VDD1_19") (pintype "power_in"))
      (node (ref "U1") (pin "32") (pinfunction "VDD2_32") (pintype "power_in"))
      (node (ref "U1") (pin "48") (pinfunction "VDD3_48") (pintype "power_in"))
      (node (ref "U1") (pin "64") (pinfunction "VDD4_64") (pintype "power_in"))
      (node (ref "U2") (pin "8") (pinfunction "VDD_8") (pintype "bidirectional"))
    )
    (net (code "107") (name "unconnected-(U2-A0-Pad1)") (class "Default")
      (node (ref "U2") (pin "1") (pinfunction "A0_1") (pintype "bidirectional"))
    )
    (net (code "108") (name "unconnected-(U2-A1-Pad2)") (class "Default")
      (node (ref "U2") (pin "2") (pinfunction "A1_2") (pintype "bidirectional"))
    )
    (net (code "109") (name "unconnected-(U2-A2-Pad3)") (class "Default")
      (node (ref "U2") (pin "3") (pinfunction "A2_3") (pintype "bidirectional"))
    )
    (net (code "110") (name "unconnected-(U2-WP-Pad7)") (class "Default")
      (node (ref "U2") (pin "7") (pinfunction "WP_7") (pintype "bidirectional"))
    )
  )
)
